# TopBee2_2V.net
KiCad netlist of a schematic drawn in EAGLE
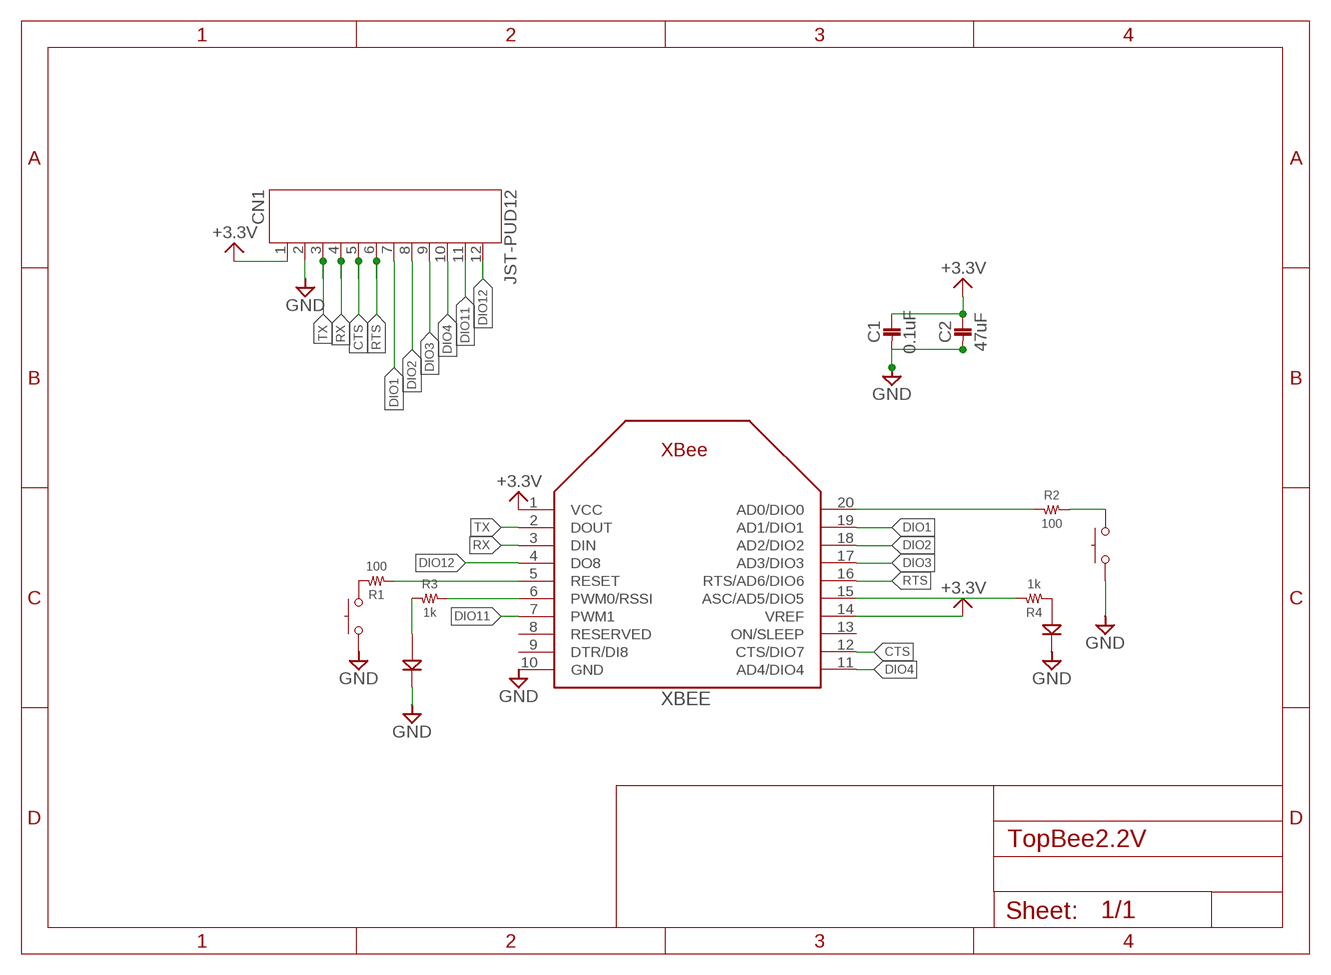
[diagram p0: schematic, sheet 1]

(export (version "E")
  (design (tool "Eeschema 10.0.6"))
  (components
    (comp (ref "C1")
      (value "0.1uF")
      (footprint "eagle-import:1608")
      (libsource (lib "eagle-import") (part "1608"))
    )
    (comp (ref "C2")
      (value "47uF")
      (footprint "eagle-import:3225")
      (libsource (lib "eagle-import") (part "3225"))
    )
    (comp (ref "CN1")
      (value "JST-PUD12")
      (footprint "eagle-import:JST-PUD12")
      (libsource (lib "eagle-import") (part "JST-PUD12"))
    )
    (comp (ref "COMM")
      (value "SKRPACE010")
      (footprint "eagle-import:SKRP")
      (libsource (lib "eagle-import") (part "SKRPACE010"))
    )
    (comp (ref "LEDB")
      (value "1608")
      (footprint "eagle-import:1608")
      (libsource (lib "eagle-import") (part "10_LED_1608"))
    )
    (comp (ref "LEDR")
      (value "1608")
      (footprint "eagle-import:1608")
      (libsource (lib "eagle-import") (part "10_LED_1608"))
    )
    (comp (ref "R1")
      (value "100")
      (footprint "eagle-import:1608")
      (libsource (lib "eagle-import") (part "RESISTOR__SMD"))
    )
    (comp (ref "R2")
      (value "100")
      (footprint "eagle-import:1608")
      (libsource (lib "eagle-import") (part "RESISTOR__SMD"))
    )
    (comp (ref "R3")
      (value "1k")
      (footprint "eagle-import:1608")
      (libsource (lib "eagle-import") (part "RESISTOR__SMD"))
    )
    (comp (ref "R4")
      (value "1k")
      (footprint "eagle-import:1608")
      (libsource (lib "eagle-import") (part "RESISTOR__SMD"))
    )
    (comp (ref "RESET")
      (value "SKRPACE010")
      (footprint "eagle-import:SKRP")
      (libsource (lib "eagle-import") (part "SKRPACE010"))
    )
    (comp (ref "XBEE")
      (value "XBEE")
      (footprint "eagle-import:XBEE")
      (libsource (lib "eagle-import") (part "XBEE"))
    )
  )
  (nets
    (net (code "1") (name "+3.3V") (class "Default")
      (node (ref "C1") (pin "P$1") (pinfunction "1_P$1") (pintype "passive"))
      (node (ref "C2") (pin "P$1") (pinfunction "1_P$1") (pintype "passive"))
      (node (ref "CN1") (pin "1") (pinfunction "1_1") (pintype "passive"))
      (node (ref "XBEE") (pin "1") (pinfunction "VCC_1") (pintype "power_in"))
      (node (ref "XBEE") (pin "14") (pinfunction "VREF_14") (pintype "input"))
    )
    (net (code "2") (name "CTS") (class "Default")
      (node (ref "CN1") (pin "5") (pinfunction "5_5") (pintype "passive"))
      (node (ref "XBEE") (pin "12") (pinfunction "CTS/DIO7_12") (pintype "bidirectional"))
    )
    (net (code "3") (name "DIO1") (class "Default")
      (node (ref "CN1") (pin "7") (pinfunction "7_7") (pintype "passive"))
      (node (ref "XBEE") (pin "19") (pinfunction "AD1/DIO1_19") (pintype "bidirectional"))
    )
    (net (code "4") (name "DIO2") (class "Default")
      (node (ref "CN1") (pin "8") (pinfunction "8_8") (pintype "passive"))
      (node (ref "XBEE") (pin "18") (pinfunction "AD2/DIO2_18") (pintype "bidirectional"))
    )
    (net (code "5") (name "DIO3") (class "Default")
      (node (ref "CN1") (pin "9") (pinfunction "9_9") (pintype "passive"))
      (node (ref "XBEE") (pin "17") (pinfunction "AD3/DIO3_17") (pintype "bidirectional"))
    )
    (net (code "6") (name "DIO4") (class "Default")
      (node (ref "CN1") (pin "10") (pinfunction "10_10") (pintype "passive"))
      (node (ref "XBEE") (pin "11") (pinfunction "AD4/DIO4_11") (pintype "bidirectional"))
    )
    (net (code "7") (name "DIO11") (class "Default")
      (node (ref "CN1") (pin "11") (pinfunction "11_11") (pintype "passive"))
      (node (ref "XBEE") (pin "7") (pinfunction "PWM1_7") (pintype "output"))
    )
    (net (code "8") (name "DIO12") (class "Default")
      (node (ref "CN1") (pin "12") (pinfunction "12_12") (pintype "passive"))
      (node (ref "XBEE") (pin "4") (pinfunction "DO8_4") (pintype "output"))
    )
    (net (code "9") (name "GND") (class "Default")
      (node (ref "C1") (pin "P$2") (pinfunction "2_P$2") (pintype "passive"))
      (node (ref "C2") (pin "P$2") (pinfunction "2_P$2") (pintype "passive"))
      (node (ref "CN1") (pin "2") (pinfunction "2_2") (pintype "passive"))
      (node (ref "COMM") (pin "3") (pinfunction "P$2_3") (pintype "bidirectional"))
      (node (ref "COMM") (pin "4") (pinfunction "P$2_4") (pintype "bidirectional"))
      (node (ref "LEDB") (pin "2") (pinfunction "K_2") (pintype "bidirectional"))
      (node (ref "LEDR") (pin "2") (pinfunction "K_2") (pintype "bidirectional"))
      (node (ref "RESET") (pin "3") (pinfunction "P$2_3") (pintype "bidirectional"))
      (node (ref "RESET") (pin "4") (pinfunction "P$2_4") (pintype "bidirectional"))
      (node (ref "XBEE") (pin "10") (pinfunction "GND_10") (pintype "power_in"))
    )
    (net (code "10") (name "Net-(LEDB-A)") (class "Default")
      (node (ref "LEDB") (pin "1") (pinfunction "A_1") (pintype "bidirectional"))
      (node (ref "R3") (pin "1") (pinfunction "P$1_1") (pintype "passive"))
    )
    (net (code "11") (name "Net-(LEDR-A)") (class "Default")
      (node (ref "LEDR") (pin "1") (pinfunction "A_1") (pintype "bidirectional"))
      (node (ref "R4") (pin "1") (pinfunction "P$1_1") (pintype "passive"))
    )
    (net (code "12") (name "Net-(R1-P$1)") (class "Default")
      (node (ref "R1") (pin "1") (pinfunction "P$1_1") (pintype "passive"))
      (node (ref "XBEE") (pin "5") (pinfunction "RESET_5") (pintype "input"))
    )
    (net (code "13") (name "Net-(R1-P$2)") (class "Default")
      (node (ref "R1") (pin "2") (pinfunction "P$2_2") (pintype "passive"))
      (node (ref "RESET") (pin "1") (pinfunction "P$1_1") (pintype "bidirectional"))
      (node (ref "RESET") (pin "2") (pinfunction "P$1_2") (pintype "bidirectional"))
    )
    (net (code "14") (name "Net-(R2-P$1)") (class "Default")
      (node (ref "R2") (pin "1") (pinfunction "P$1_1") (pintype "passive"))
      (node (ref "XBEE") (pin "20") (pinfunction "AD0/DIO0_20") (pintype "bidirectional"))
    )
    (net (code "15") (name "Net-(R2-P$2)") (class "Default")
      (node (ref "COMM") (pin "1") (pinfunction "P$1_1") (pintype "bidirectional"))
      (node (ref "COMM") (pin "2") (pinfunction "P$1_2") (pintype "bidirectional"))
      (node (ref "R2") (pin "2") (pinfunction "P$2_2") (pintype "passive"))
    )
    (net (code "16") (name "Net-(R3-P$2)") (class "Default")
      (node (ref "R3") (pin "2") (pinfunction "P$2_2") (pintype "passive"))
      (node (ref "XBEE") (pin "6") (pinfunction "PWM0/RSSI_6") (pintype "output"))
    )
    (net (code "17") (name "Net-(R4-P$2)") (class "Default")
      (node (ref "R4") (pin "2") (pinfunction "P$2_2") (pintype "passive"))
      (node (ref "XBEE") (pin "15") (pinfunction "ASC/AD5/DIO5_15") (pintype "bidirectional"))
    )
    (net (code "18") (name "RTS") (class "Default")
      (node (ref "CN1") (pin "6") (pinfunction "6_6") (pintype "passive"))
      (node (ref "XBEE") (pin "16") (pinfunction "RTS/AD6/DIO6_16") (pintype "bidirectional"))
    )
    (net (code "19") (name "RX") (class "Default")
      (node (ref "CN1") (pin "4") (pinfunction "4_4") (pintype "passive"))
      (node (ref "XBEE") (pin "3") (pinfunction "DIN_3") (pintype "input"))
    )
    (net (code "20") (name "TX") (class "Default")
      (node (ref "CN1") (pin "3") (pinfunction "3_3") (pintype "passive"))
      (node (ref "XBEE") (pin "2") (pinfunction "DOUT_2") (pintype "output"))
    )
    (net (code "21") (name "unconnected-(XBEE-DTR{slash}DI8-Pad9)") (class "Default")
      (node (ref "XBEE") (pin "9") (pinfunction "DTR/DI8_9") (pintype "input"))
    )
    (net (code "22") (name "unconnected-(XBEE-ON{slash}SLEEP-Pad13)") (class "Default")
      (node (ref "XBEE") (pin "13") (pinfunction "ON/SLEEP_13") (pintype "output"))
    )
    (net (code "23") (name "unconnected-(XBEE-RESERVED-Pad8)") (class "Default")
      (node (ref "XBEE") (pin "8") (pinfunction "RESERVED_8") (pintype "no_connect"))
    )
  )
)
